# MCU.net
KiCad netlist of a schematic drawn in Altium Designer
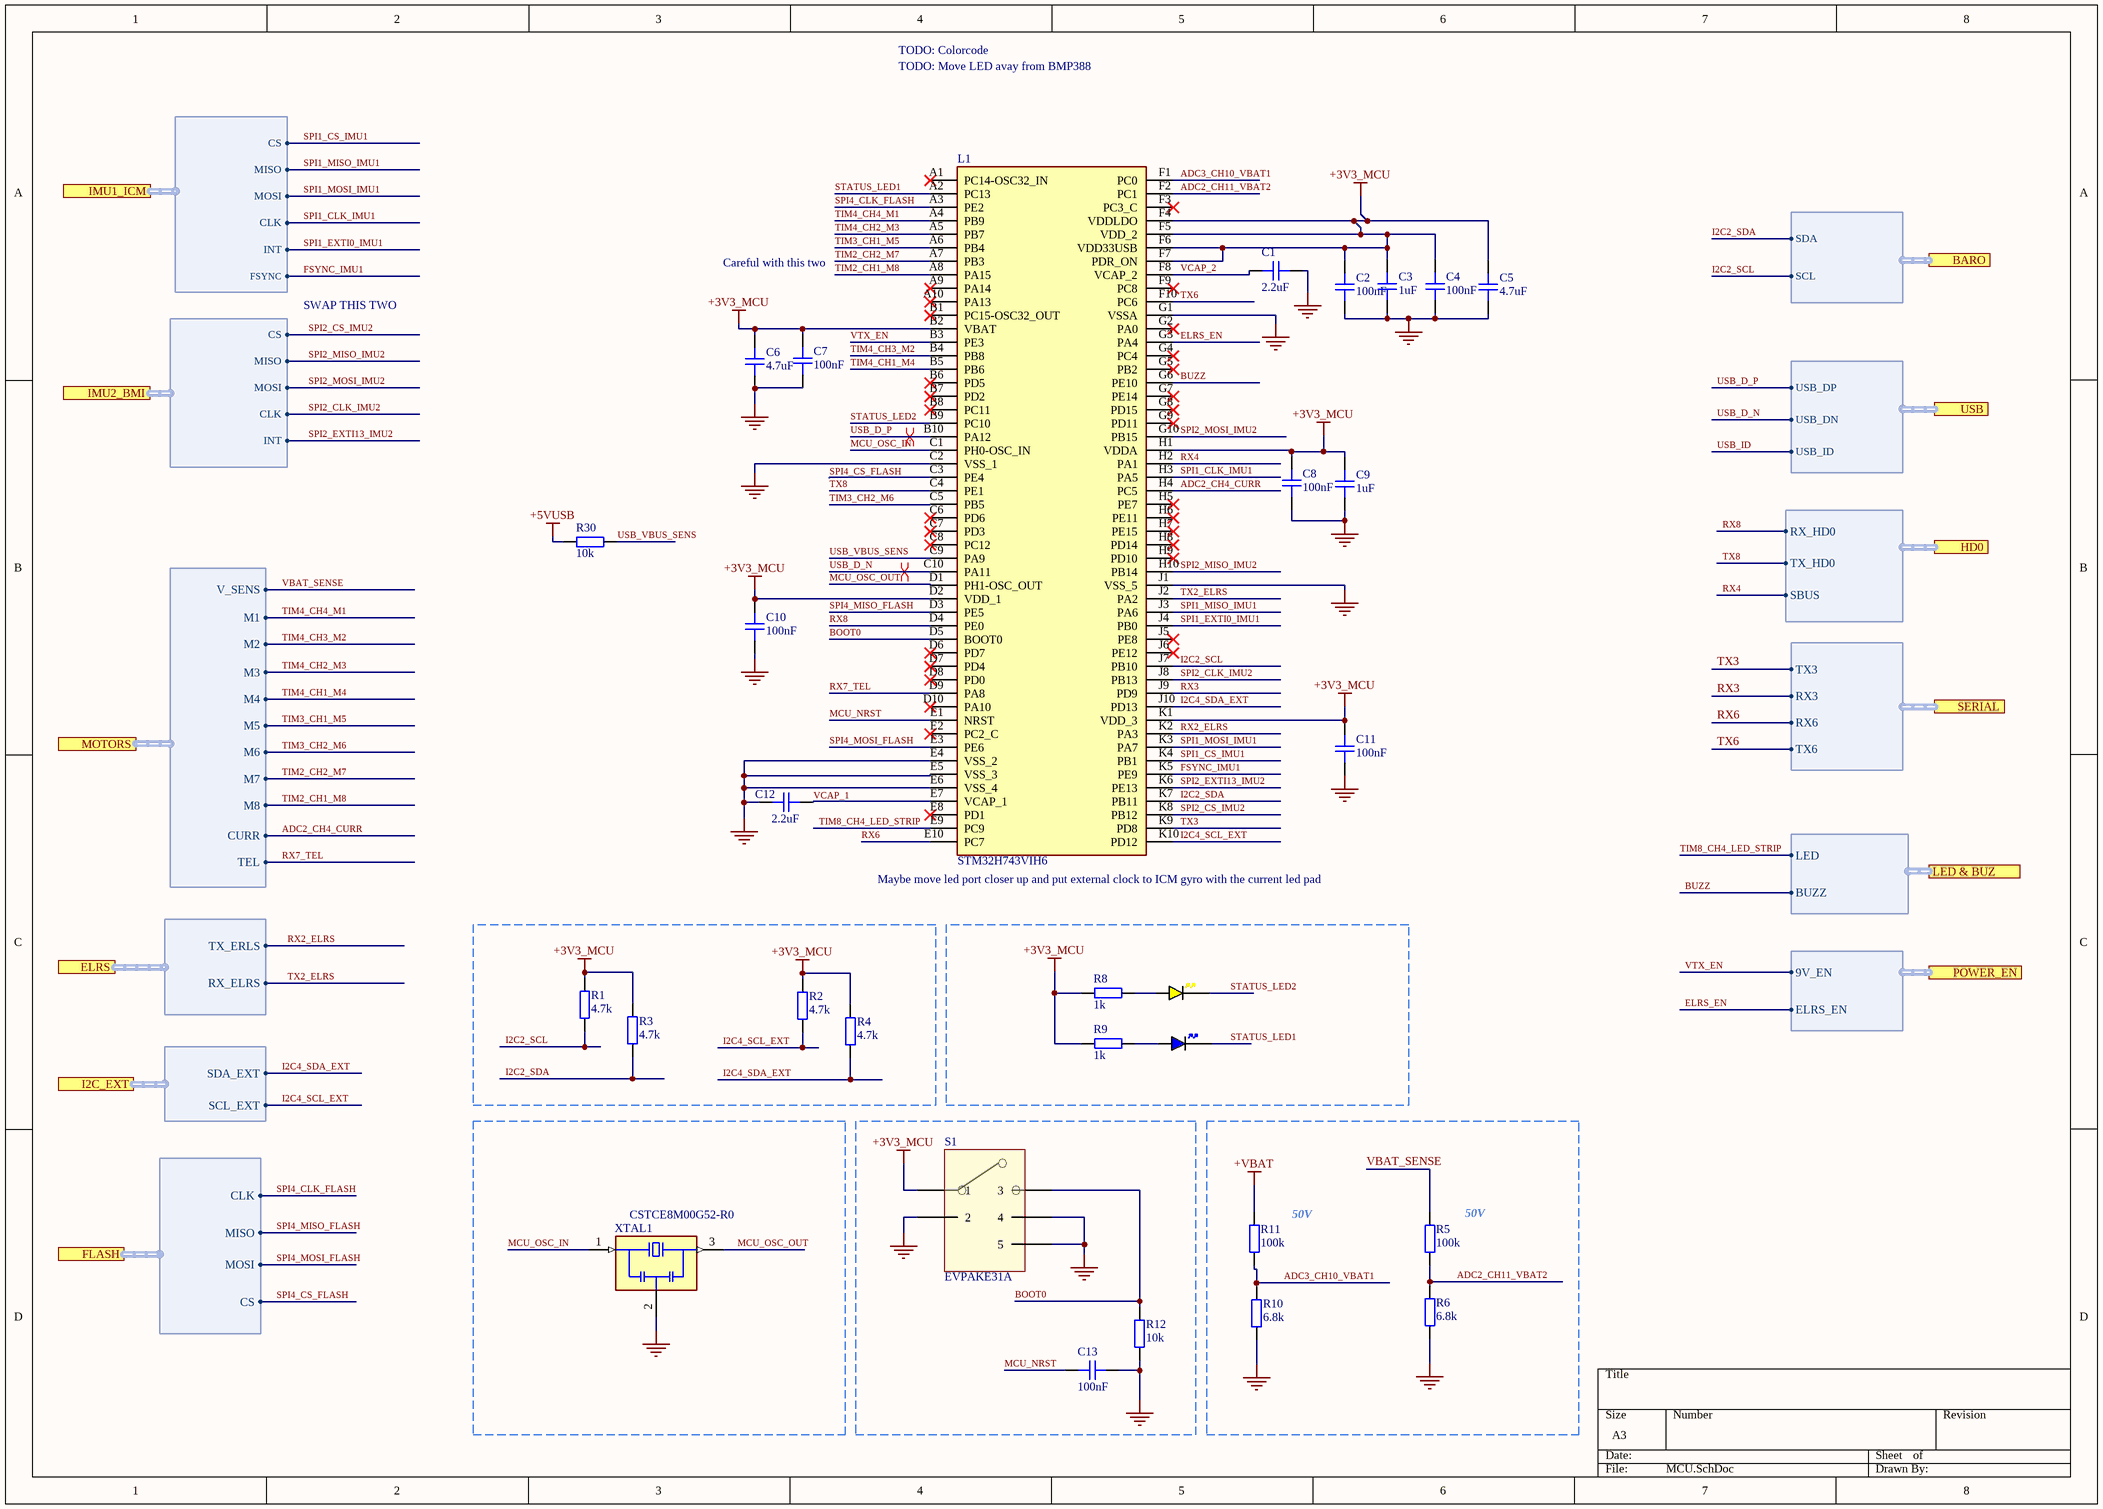
[diagram p0: MCU.SchDoc]

(export (version "E")
  (design (tool "Eeschema 10.0.6"))
  (components
    (comp (ref "C1")
      (value "2.2uF")
      (footprint "CAP_0402")
      (description "Capacitor SMD 0402")
      (libsource (lib "Schematic-Lib-PhilsLab") (part "CAP_0402"))
    )
    (comp (ref "C2")
      (value "100nF")
      (footprint "CAP_0201")
      (description "Capacitor SMD 0201")
      (libsource (lib "Schematic-Lib-PhilsLab") (part "CAP_0201"))
    )
    (comp (ref "C3")
      (value "1uF")
      (footprint "CAP_0402")
      (description "Capacitor SMD 0402")
      (libsource (lib "Schematic-Lib-PhilsLab") (part "CAP_0402"))
    )
    (comp (ref "C4")
      (value "100nF")
      (footprint "CAP_0201")
      (description "Capacitor SMD 0201")
      (libsource (lib "Schematic-Lib-PhilsLab") (part "CAP_0201"))
    )
    (comp (ref "C5")
      (value "4.7uF")
      (footprint "CAP_0402")
      (description "Capacitor SMD 0402")
      (libsource (lib "Schematic-Lib-PhilsLab") (part "CAP_0402"))
    )
    (comp (ref "C6")
      (value "4.7uF")
      (footprint "CAP_0402")
      (description "Capacitor SMD 0402")
      (libsource (lib "Schematic-Lib-PhilsLab") (part "CAP_0402"))
    )
    (comp (ref "C7")
      (value "100nF")
      (footprint "CAP_0201")
      (description "Capacitor SMD 0201")
      (libsource (lib "Schematic-Lib-PhilsLab") (part "CAP_0201"))
    )
    (comp (ref "C8")
      (value "100nF")
      (footprint "CAP_0201")
      (description "Capacitor SMD 0201")
      (libsource (lib "Schematic-Lib-PhilsLab") (part "CAP_0201"))
    )
    (comp (ref "C9")
      (value "1uF")
      (footprint "CAP_0402")
      (description "Capacitor SMD 0402")
      (libsource (lib "Schematic-Lib-PhilsLab") (part "CAP_0402"))
    )
    (comp (ref "C10")
      (value "100nF")
      (footprint "CAP_0201")
      (description "Capacitor SMD 0201")
      (libsource (lib "Schematic-Lib-PhilsLab") (part "CAP_0201"))
    )
    (comp (ref "C11")
      (value "100nF")
      (footprint "CAP_0201")
      (description "Capacitor SMD 0201")
      (libsource (lib "Schematic-Lib-PhilsLab") (part "CAP_0201"))
    )
    (comp (ref "C12")
      (value "2.2uF")
      (footprint "CAP_0402")
      (description "Capacitor SMD 0402")
      (libsource (lib "Schematic-Lib-PhilsLab") (part "CAP_0402"))
    )
    (comp (ref "C13")
      (value "100nF")
      (footprint "CAP_0201")
      (description "Capacitor SMD 0201")
      (libsource (lib "Schematic-Lib-PhilsLab") (part "CAP_0201"))
    )
    (comp (ref "L1")
      (value "STM32H743VIH6")
      (footprint "SamacSys:BGA100C80P10X10_800X800X110")
      (description "Inductor")
      (fields (field (name "MOUSER PART NUMBER") "511-STM32H743VIH6"))
      (libsource (lib "*") (part "STM32H743VIH6"))
    )
    (comp (ref "LED1")
      (value "YELLOW")
      (footprint "LED_0402_YELLOW")
      (description "LED 0402 YELLOW SMD")
      (libsource (lib "Schematic-Lib-PhilsLab") (part "LED_0402_YELLOW"))
    )
    (comp (ref "LED2")
      (value "BLUE")
      (footprint "LED_0402_BLUE")
      (description "LED 0402 BLUE SMD")
      (libsource (lib "Schematic-Lib-PhilsLab") (part "LED_0402_BLUE"))
    )
    (comp (ref "R1")
      (value "4.7k")
      (footprint "RES_0201")
      (description "Resistor SMD 0201")
      (libsource (lib "Schematic-Lib-PhilsLab") (part "RES_0201"))
    )
    (comp (ref "R2")
      (value "4.7k")
      (footprint "RES_0201")
      (description "Resistor SMD 0201")
      (libsource (lib "Schematic-Lib-PhilsLab") (part "RES_0201"))
    )
    (comp (ref "R3")
      (value "4.7k")
      (footprint "RES_0201")
      (description "Resistor SMD 0201")
      (libsource (lib "Schematic-Lib-PhilsLab") (part "RES_0201"))
    )
    (comp (ref "R4")
      (value "4.7k")
      (footprint "RES_0201")
      (description "Resistor SMD 0201")
      (libsource (lib "Schematic-Lib-PhilsLab") (part "RES_0201"))
    )
    (comp (ref "R5")
      (value "100k")
      (footprint "RES_0402")
      (description "Resistor SMD 0402")
      (libsource (lib "Schematic-Lib-PhilsLab") (part "RES_0402"))
    )
    (comp (ref "R6")
      (value "6.8k")
      (footprint "RES_0201")
      (description "Resistor SMD 0201")
      (libsource (lib "Schematic-Lib-PhilsLab") (part "RES_0201"))
    )
    (comp (ref "R8")
      (value "1k")
      (footprint "RES_0201")
      (description "Resistor SMD 0201")
      (libsource (lib "Schematic-Lib-PhilsLab") (part "RES_0201"))
    )
    (comp (ref "R9")
      (value "1k")
      (footprint "RES_0201")
      (description "Resistor SMD 0201")
      (libsource (lib "Schematic-Lib-PhilsLab") (part "RES_0201"))
    )
    (comp (ref "R10")
      (value "6.8k")
      (footprint "RES_0201")
      (description "Resistor SMD 0201")
      (libsource (lib "Schematic-Lib-PhilsLab") (part "RES_0201"))
    )
    (comp (ref "R11")
      (value "100k")
      (footprint "RES_0402")
      (description "Resistor SMD 0402")
      (libsource (lib "Schematic-Lib-PhilsLab") (part "RES_0402"))
    )
    (comp (ref "R12")
      (value "10k")
      (footprint "RES_0201")
      (description "Resistor SMD 0201")
      (libsource (lib "Schematic-Lib-PhilsLab") (part "RES_0201"))
    )
    (comp (ref "R30")
      (value "10k")
      (footprint "RES_0201")
      (description "Resistor SMD 0201")
      (libsource (lib "Schematic-Lib-PhilsLab") (part "RES_0201"))
    )
    (comp (ref "S1")
      (value "EVPAKE31A")
      (footprint "EVPAKE31A")
      (libsource (lib "Schematic-Lib-Singu") (part "EVPAKE31A"))
    )
    (comp (ref "XTAL1")
      (value "CSTCE8M00G52-R0")
      (footprint "OSC_CSTCE8M00G52-R0")
      (description "8MHz Ceramic Resonator Built in Capacitor 10pF Â±0.2% -20Â°C ~ 80Â°C Surface Mount")
      (fields (field (name "MF") "Murata"))
      (libsource (lib "Schematic-Lib-Singu") (part "CSTCE8M00G52-R0"))
    )
  )
  (nets
    (net (code "12") (name "+3V3_MCU") (class "Default")
      (node (ref "C10") (pin "2") (pinfunction "2_2") (pintype "passive"))
      (node (ref "C11") (pin "2") (pinfunction "2_2") (pintype "passive"))
      (node (ref "C2") (pin "2") (pinfunction "2_2") (pintype "passive"))
      (node (ref "C3") (pin "2") (pinfunction "2_2") (pintype "passive"))
      (node (ref "C4") (pin "2") (pinfunction "2_2") (pintype "passive"))
      (node (ref "C5") (pin "2") (pinfunction "2_2") (pintype "passive"))
      (node (ref "C6") (pin "2") (pinfunction "2_2") (pintype "passive"))
      (node (ref "C7") (pin "2") (pinfunction "2_2") (pintype "passive"))
      (node (ref "C8") (pin "2") (pinfunction "2_2") (pintype "passive"))
      (node (ref "C9") (pin "2") (pinfunction "2_2") (pintype "passive"))
      (node (ref "L1") (pin "B2") (pinfunction "VBAT_B2") (pintype "passive"))
      (node (ref "L1") (pin "D2") (pinfunction "VDD_1_D2") (pintype "passive"))
      (node (ref "L1") (pin "F4") (pinfunction "VDDLDO_F4") (pintype "passive"))
      (node (ref "L1") (pin "F5") (pinfunction "VDD_2_F5") (pintype "passive"))
      (node (ref "L1") (pin "F6") (pinfunction "VDD33USB_F6") (pintype "passive"))
      (node (ref "L1") (pin "F7") (pinfunction "PDR_ON_F7") (pintype "passive"))
      (node (ref "L1") (pin "H1") (pinfunction "VDDA_H1") (pintype "passive"))
      (node (ref "L1") (pin "K1") (pinfunction "VDD_3_K1") (pintype "passive"))
      (node (ref "R1") (pin "2") (pinfunction "2_2") (pintype "passive"))
      (node (ref "R2") (pin "2") (pinfunction "2_2") (pintype "passive"))
      (node (ref "R3") (pin "2") (pinfunction "2_2") (pintype "passive"))
      (node (ref "R4") (pin "2") (pinfunction "2_2") (pintype "passive"))
      (node (ref "R8") (pin "1") (pinfunction "1_1") (pintype "passive"))
      (node (ref "R9") (pin "1") (pinfunction "1_1") (pintype "passive"))
      (node (ref "S1") (pin "1") (pinfunction "1_1") (pintype "passive"))
    )
    (net (code "13") (name "+5VUSB") (class "Default")
      (node (ref "R30") (pin "1") (pinfunction "1_1") (pintype "passive"))
    )
    (net (code "14") (name "+VBAT") (class "Default")
      (node (ref "R11") (pin "2") (pinfunction "2_2") (pintype "passive"))
    )
    (net (code "16") (name "/ADC2_CH4_CURR") (class "Default")
      (node (ref "L1") (pin "H4") (pinfunction "PC5_H4") (pintype "passive"))
    )
    (net (code "17") (name "/ADC2_CH11_VBAT2") (class "Default")
      (node (ref "L1") (pin "F2") (pinfunction "PC1_F2") (pintype "passive"))
      (node (ref "R5") (pin "1") (pinfunction "1_1") (pintype "passive"))
      (node (ref "R6") (pin "2") (pinfunction "2_2") (pintype "passive"))
    )
    (net (code "18") (name "/ADC3_CH10_VBAT1") (class "Default")
      (node (ref "L1") (pin "F1") (pinfunction "PC0_F1") (pintype "passive"))
      (node (ref "R10") (pin "2") (pinfunction "2_2") (pintype "passive"))
      (node (ref "R11") (pin "1") (pinfunction "1_1") (pintype "passive"))
    )
    (net (code "19") (name "/BOOT0") (class "Default")
      (node (ref "L1") (pin "D5") (pinfunction "BOOT0_D5") (pintype "passive"))
      (node (ref "R12") (pin "2") (pinfunction "2_2") (pintype "passive"))
      (node (ref "S1") (pin "3") (pinfunction "3_3") (pintype "passive"))
    )
    (net (code "20") (name "/BUZZ") (class "Default")
      (node (ref "L1") (pin "G6") (pinfunction "PE10_G6") (pintype "passive"))
    )
    (net (code "21") (name "/ELRS_EN") (class "Default")
      (node (ref "L1") (pin "G3") (pinfunction "PA4_G3") (pintype "passive"))
    )
    (net (code "22") (name "/FSYNC_IMU1") (class "Default")
      (node (ref "L1") (pin "K5") (pinfunction "PE9_K5") (pintype "passive"))
    )
    (net (code "23") (name "/I2C2_SCL") (class "Default")
      (node (ref "L1") (pin "J7") (pinfunction "PB10_J7") (pintype "passive"))
      (node (ref "R1") (pin "1") (pinfunction "1_1") (pintype "passive"))
    )
    (net (code "24") (name "/I2C2_SDA") (class "Default")
      (node (ref "L1") (pin "K7") (pinfunction "PB11_K7") (pintype "passive"))
      (node (ref "R3") (pin "1") (pinfunction "1_1") (pintype "passive"))
    )
    (net (code "25") (name "/I2C4_SCL_EXT") (class "Default")
      (node (ref "L1") (pin "K10") (pinfunction "PD12_K10") (pintype "passive"))
      (node (ref "R2") (pin "1") (pinfunction "1_1") (pintype "passive"))
    )
    (net (code "26") (name "/I2C4_SDA_EXT") (class "Default")
      (node (ref "L1") (pin "J10") (pinfunction "PD13_J10") (pintype "passive"))
      (node (ref "R4") (pin "1") (pinfunction "1_1") (pintype "passive"))
    )
    (net (code "27") (name "/MCU_NRST") (class "Default")
      (node (ref "C13") (pin "1") (pinfunction "1_1") (pintype "passive"))
      (node (ref "L1") (pin "E1") (pinfunction "NRST_E1") (pintype "passive"))
    )
    (net (code "28") (name "/MCU_OSC_IN") (class "Default")
      (node (ref "L1") (pin "C1") (pinfunction "PH0-OSC_IN_C1") (pintype "passive"))
      (node (ref "XTAL1") (pin "1") (pinfunction "IN_1") (pintype "input"))
    )
    (net (code "29") (name "/MCU_OSC_OUT") (class "Default")
      (node (ref "L1") (pin "D1") (pinfunction "PH1-OSC_OUT_D1") (pintype "passive"))
      (node (ref "XTAL1") (pin "3") (pinfunction "OUT_3") (pintype "output"))
    )
    (net (code "30") (name "/RX2_ELRS") (class "Default")
      (node (ref "L1") (pin "K2") (pinfunction "PA3_K2") (pintype "passive"))
    )
    (net (code "31") (name "/RX3") (class "Default")
      (node (ref "L1") (pin "J9") (pinfunction "PD9_J9") (pintype "passive"))
    )
    (net (code "32") (name "/RX4") (class "Default")
      (node (ref "L1") (pin "H2") (pinfunction "PA1_H2") (pintype "passive"))
    )
    (net (code "33") (name "/RX6") (class "Default")
      (node (ref "L1") (pin "E10") (pinfunction "PC7_E10") (pintype "passive"))
    )
    (net (code "34") (name "/RX7_TEL") (class "Default")
      (node (ref "L1") (pin "D9") (pinfunction "PA8_D9") (pintype "passive"))
    )
    (net (code "35") (name "/RX8") (class "Default")
      (node (ref "L1") (pin "D4") (pinfunction "PE0_D4") (pintype "passive"))
    )
    (net (code "36") (name "/SPI1_CLK_IMU1") (class "Default")
      (node (ref "L1") (pin "H3") (pinfunction "PA5_H3") (pintype "passive"))
    )
    (net (code "37") (name "/SPI1_CS_IMU1") (class "Default")
      (node (ref "L1") (pin "K4") (pinfunction "PB1_K4") (pintype "passive"))
    )
    (net (code "38") (name "/SPI1_EXTI0_IMU1") (class "Default")
      (node (ref "L1") (pin "J4") (pinfunction "PB0_J4") (pintype "passive"))
    )
    (net (code "39") (name "/SPI1_MISO_IMU1") (class "Default")
      (node (ref "L1") (pin "J3") (pinfunction "PA6_J3") (pintype "passive"))
    )
    (net (code "40") (name "/SPI1_MOSI_IMU1") (class "Default")
      (node (ref "L1") (pin "K3") (pinfunction "PA7_K3") (pintype "passive"))
    )
    (net (code "41") (name "/SPI2_CLK_IMU2") (class "Default")
      (node (ref "L1") (pin "J8") (pinfunction "PB13_J8") (pintype "passive"))
    )
    (net (code "42") (name "/SPI2_CS_IMU2") (class "Default")
      (node (ref "L1") (pin "K8") (pinfunction "PB12_K8") (pintype "passive"))
    )
    (net (code "43") (name "/SPI2_EXTI13_IMU2") (class "Default")
      (node (ref "L1") (pin "K6") (pinfunction "PE13_K6") (pintype "passive"))
    )
    (net (code "44") (name "/SPI2_MISO_IMU2") (class "Default")
      (node (ref "L1") (pin "H10") (pinfunction "PB14_H10") (pintype "passive"))
    )
    (net (code "45") (name "/SPI2_MOSI_IMU2") (class "Default")
      (node (ref "L1") (pin "G10") (pinfunction "PB15_G10") (pintype "passive"))
    )
    (net (code "46") (name "/SPI4_CLK_FLASH") (class "Default")
      (node (ref "L1") (pin "A3") (pinfunction "PE2_A3") (pintype "passive"))
    )
    (net (code "47") (name "/SPI4_CS_FLASH") (class "Default")
      (node (ref "L1") (pin "C3") (pinfunction "PE4_C3") (pintype "passive"))
    )
    (net (code "48") (name "/SPI4_MISO_FLASH") (class "Default")
      (node (ref "L1") (pin "D3") (pinfunction "PE5_D3") (pintype "passive"))
    )
    (net (code "49") (name "/SPI4_MOSI_FLASH") (class "Default")
      (node (ref "L1") (pin "E3") (pinfunction "PE6_E3") (pintype "passive"))
    )
    (net (code "50") (name "/STATUS_LED1") (class "Default")
      (node (ref "L1") (pin "A2") (pinfunction "PC13_A2") (pintype "passive"))
      (node (ref "LED2") (pin "K") (pinfunction "K_K") (pintype "passive"))
    )
    (net (code "51") (name "/STATUS_LED2") (class "Default")
      (node (ref "L1") (pin "B9") (pinfunction "PC10_B9") (pintype "passive"))
      (node (ref "LED1") (pin "K") (pinfunction "K_K") (pintype "passive"))
    )
    (net (code "52") (name "/TIM2_CH1_M8") (class "Default")
      (node (ref "L1") (pin "A8") (pinfunction "PA15_A8") (pintype "passive"))
    )
    (net (code "53") (name "/TIM2_CH2_M7") (class "Default")
      (node (ref "L1") (pin "A7") (pinfunction "PB3_A7") (pintype "passive"))
    )
    (net (code "54") (name "/TIM3_CH1_M5") (class "Default")
      (node (ref "L1") (pin "A6") (pinfunction "PB4_A6") (pintype "passive"))
    )
    (net (code "55") (name "/TIM3_CH2_M6") (class "Default")
      (node (ref "L1") (pin "C5") (pinfunction "PB5_C5") (pintype "passive"))
    )
    (net (code "56") (name "/TIM4_CH1_M4") (class "Default")
      (node (ref "L1") (pin "B5") (pinfunction "PB6_B5") (pintype "passive"))
    )
    (net (code "57") (name "/TIM4_CH2_M3") (class "Default")
      (node (ref "L1") (pin "A5") (pinfunction "PB7_A5") (pintype "passive"))
    )
    (net (code "58") (name "/TIM4_CH3_M2") (class "Default")
      (node (ref "L1") (pin "B4") (pinfunction "PB8_B4") (pintype "passive"))
    )
    (net (code "59") (name "/TIM4_CH4_M1") (class "Default")
      (node (ref "L1") (pin "A4") (pinfunction "PB9_A4") (pintype "passive"))
    )
    (net (code "60") (name "/TIM8_CH4_LED_STRIP") (class "Default")
      (node (ref "L1") (pin "E9") (pinfunction "PC9_E9") (pintype "passive"))
    )
    (net (code "61") (name "/TX2_ELRS") (class "Default")
      (node (ref "L1") (pin "J2") (pinfunction "PA2_J2") (pintype "passive"))
    )
    (net (code "62") (name "/TX3") (class "Default")
      (node (ref "L1") (pin "K9") (pinfunction "PD8_K9") (pintype "passive"))
    )
    (net (code "63") (name "/TX6") (class "Default")
      (node (ref "L1") (pin "F10") (pinfunction "PC6_F10") (pintype "passive"))
    )
    (net (code "64") (name "/TX8") (class "Default")
      (node (ref "L1") (pin "C4") (pinfunction "PE1_C4") (pintype "passive"))
    )
    (net (code "65") (name "/USB_D_N") (class "Default")
      (node (ref "L1") (pin "C10") (pinfunction "PA11_C10") (pintype "passive"))
    )
    (net (code "66") (name "/USB_D_P") (class "Default")
      (node (ref "L1") (pin "B10") (pinfunction "PA12_B10") (pintype "passive"))
    )
    (net (code "68") (name "/USB_VBUS_SENS") (class "Default")
      (node (ref "L1") (pin "C9") (pinfunction "PA9_C9") (pintype "passive"))
      (node (ref "R30") (pin "2") (pinfunction "2_2") (pintype "passive"))
    )
    (net (code "69") (name "/VBAT_SENSE") (class "Default")
      (node (ref "R5") (pin "2") (pinfunction "2_2") (pintype "passive"))
    )
    (net (code "70") (name "/VCAP_1") (class "Default")
      (node (ref "C12") (pin "2") (pinfunction "2_2") (pintype "passive"))
      (node (ref "L1") (pin "E7") (pinfunction "VCAP_1_E7") (pintype "passive"))
    )
    (net (code "71") (name "/VCAP_2") (class "Default")
      (node (ref "C1") (pin "1") (pinfunction "1_1") (pintype "passive"))
      (node (ref "L1") (pin "F8") (pinfunction "VCAP_2_F8") (pintype "passive"))
    )
    (net (code "72") (name "/VTX_EN") (class "Default")
      (node (ref "L1") (pin "B3") (pinfunction "PE3_B3") (pintype "passive"))
    )
    (net (code "85") (name "GND") (class "Default")
      (node (ref "C1") (pin "2") (pinfunction "2_2") (pintype "passive"))
      (node (ref "C10") (pin "1") (pinfunction "1_1") (pintype "passive"))
      (node (ref "C11") (pin "1") (pinfunction "1_1") (pintype "passive"))
      (node (ref "C12") (pin "1") (pinfunction "1_1") (pintype "passive"))
      (node (ref "C13") (pin "2") (pinfunction "2_2") (pintype "passive"))
      (node (ref "C2") (pin "1") (pinfunction "1_1") (pintype "passive"))
      (node (ref "C3") (pin "1") (pinfunction "1_1") (pintype "passive"))
      (node (ref "C4") (pin "1") (pinfunction "1_1") (pintype "passive"))
      (node (ref "C5") (pin "1") (pinfunction "1_1") (pintype "passive"))
      (node (ref "C6") (pin "1") (pinfunction "1_1") (pintype "passive"))
      (node (ref "C7") (pin "1") (pinfunction "1_1") (pintype "passive"))
      (node (ref "C8") (pin "1") (pinfunction "1_1") (pintype "passive"))
      (node (ref "C9") (pin "1") (pinfunction "1_1") (pintype "passive"))
      (node (ref "L1") (pin "C2") (pinfunction "VSS_1_C2") (pintype "passive"))
      (node (ref "L1") (pin "E4") (pinfunction "VSS_2_E4") (pintype "passive"))
      (node (ref "L1") (pin "E5") (pinfunction "VSS_3_E5") (pintype "passive"))
      (node (ref "L1") (pin "E6") (pinfunction "VSS_4_E6") (pintype "passive"))
      (node (ref "L1") (pin "G1") (pinfunction "VSSA_G1") (pintype "passive"))
      (node (ref "L1") (pin "J1") (pinfunction "VSS_5_J1") (pintype "passive"))
      (node (ref "R10") (pin "1") (pinfunction "1_1") (pintype "passive"))
      (node (ref "R12") (pin "1") (pinfunction "1_1") (pintype "passive"))
      (node (ref "R6") (pin "1") (pinfunction "1_1") (pintype "passive"))
      (node (ref "S1") (pin "2") (pinfunction "2_2") (pintype "passive"))
      (node (ref "S1") (pin "4") (pinfunction "4_4") (pintype "passive"))
      (node (ref "S1") (pin "5") (pinfunction "5_5") (pintype "passive"))
      (node (ref "XTAL1") (pin "2") (pinfunction "GND_2") (pintype "power_in"))
    )
    (net (code "86") (name "Net-(LED1-PadA)") (class "Default")
      (node (ref "LED1") (pin "A") (pinfunction "A_A") (pintype "passive"))
      (node (ref "R8") (pin "2") (pinfunction "2_2") (pintype "passive"))
    )
    (net (code "87") (name "Net-(LED2-PadA)") (class "Default")
      (node (ref "LED2") (pin "A") (pinfunction "A_A") (pintype "passive"))
      (node (ref "R9") (pin "2") (pinfunction "2_2") (pintype "passive"))
    )
    (net (code "88") (name "unconnected-(L1-PA0-PadG2)") (class "Default")
      (node (ref "L1") (pin "G2") (pinfunction "PA0_G2") (pintype "passive+no_connect"))
    )
    (net (code "89") (name "unconnected-(L1-PA10-PadD10)") (class "Default")
      (node (ref "L1") (pin "D10") (pinfunction "PA10_D10") (pintype "passive+no_connect"))
    )
    (net (code "90") (name "unconnected-(L1-PA13-PadA10)") (class "Default")
      (node (ref "L1") (pin "A10") (pinfunction "PA13_A10") (pintype "passive+no_connect"))
    )
    (net (code "91") (name "unconnected-(L1-PA14-PadA9)") (class "Default")
      (node (ref "L1") (pin "A9") (pinfunction "PA14_A9") (pintype "passive+no_connect"))
    )
    (net (code "92") (name "unconnected-(L1-PB2-PadG5)") (class "Default")
      (node (ref "L1") (pin "G5") (pinfunction "PB2_G5") (pintype "passive+no_connect"))
    )
    (net (code "93") (name "unconnected-(L1-PC2_C-PadE2)") (class "Default")
      (node (ref "L1") (pin "E2") (pinfunction "PC2_C_E2") (pintype "passive+no_connect"))
    )
    (net (code "94") (name "unconnected-(L1-PC3_C-PadF3)") (class "Default")
      (node (ref "L1") (pin "F3") (pinfunction "PC3_C_F3") (pintype "passive+no_connect"))
    )
    (net (code "95") (name "unconnected-(L1-PC4-PadG4)") (class "Default")
      (node (ref "L1") (pin "G4") (pinfunction "PC4_G4") (pintype "passive+no_connect"))
    )
    (net (code "96") (name "unconnected-(L1-PC8-PadF9)") (class "Default")
      (node (ref "L1") (pin "F9") (pinfunction "PC8_F9") (pintype "passive+no_connect"))
    )
    (net (code "97") (name "unconnected-(L1-PC11-PadB8)") (class "Default")
      (node (ref "L1") (pin "B8") (pinfunction "PC11_B8") (pintype "passive+no_connect"))
    )
    (net (code "98") (name "unconnected-(L1-PC12-PadC8)") (class "Default")
      (node (ref "L1") (pin "C8") (pinfunction "PC12_C8") (pintype "passive+no_connect"))
    )
    (net (code "99") (name "unconnected-(L1-PC14-OSC32_IN-PadA1)") (class "Default")
      (node (ref "L1") (pin "A1") (pinfunction "PC14-OSC32_IN_A1") (pintype "passive+no_connect"))
    )
    (net (code "100") (name "unconnected-(L1-PC15-OSC32_OUT-PadB1)") (class "Default")
      (node (ref "L1") (pin "B1") (pinfunction "PC15-OSC32_OUT_B1") (pintype "passive+no_connect"))
    )
    (net (code "101") (name "unconnected-(L1-PD0-PadD8)") (class "Default")
      (node (ref "L1") (pin "D8") (pinfunction "PD0_D8") (pintype "passive+no_connect"))
    )
    (net (code "102") (name "unconnected-(L1-PD1-PadE8)") (class "Default")
      (node (ref "L1") (pin "E8") (pinfunction "PD1_E8") (pintype "passive+no_connect"))
    )
    (net (code "103") (name "unconnected-(L1-PD2-PadB7)") (class "Default")
      (node (ref "L1") (pin "B7") (pinfunction "PD2_B7") (pintype "passive+no_connect"))
    )
    (net (code "104") (name "unconnected-(L1-PD3-PadC7)") (class "Default")
      (node (ref "L1") (pin "C7") (pinfunction "PD3_C7") (pintype "passive+no_connect"))
    )
    (net (code "105") (name "unconnected-(L1-PD4-PadD7)") (class "Default")
      (node (ref "L1") (pin "D7") (pinfunction "PD4_D7") (pintype "passive+no_connect"))
    )
    (net (code "106") (name "unconnected-(L1-PD5-PadB6)") (class "Default")
      (node (ref "L1") (pin "B6") (pinfunction "PD5_B6") (pintype "passive+no_connect"))
    )
    (net (code "107") (name "unconnected-(L1-PD6-PadC6)") (class "Default")
      (node (ref "L1") (pin "C6") (pinfunction "PD6_C6") (pintype "passive+no_connect"))
    )
    (net (code "108") (name "unconnected-(L1-PD7-PadD6)") (class "Default")
      (node (ref "L1") (pin "D6") (pinfunction "PD7_D6") (pintype "passive+no_connect"))
    )
    (net (code "109") (name "unconnected-(L1-PD10-PadH9)") (class "Default")
      (node (ref "L1") (pin "H9") (pinfunction "PD10_H9") (pintype "passive+no_connect"))
    )
    (net (code "110") (name "unconnected-(L1-PD11-PadG9)") (class "Default")
      (node (ref "L1") (pin "G9") (pinfunction "PD11_G9") (pintype "passive+no_connect"))
    )
    (net (code "111") (name "unconnected-(L1-PD14-PadH8)") (class "Default")
      (node (ref "L1") (pin "H8") (pinfunction "PD14_H8") (pintype "passive+no_connect"))
    )
    (net (code "112") (name "unconnected-(L1-PD15-PadG8)") (class "Default")
      (node (ref "L1") (pin "G8") (pinfunction "PD15_G8") (pintype "passive+no_connect"))
    )
    (net (code "113") (name "unconnected-(L1-PE7-PadH5)") (class "Default")
      (node (ref "L1") (pin "H5") (pinfunction "PE7_H5") (pintype "passive+no_connect"))
    )
    (net (code "114") (name "unconnected-(L1-PE8-PadJ5)") (class "Default")
      (node (ref "L1") (pin "J5") (pinfunction "PE8_J5") (pintype "passive+no_connect"))
    )
    (net (code "115") (name "unconnected-(L1-PE11-PadH6)") (class "Default")
      (node (ref "L1") (pin "H6") (pinfunction "PE11_H6") (pintype "passive+no_connect"))
    )
    (net (code "116") (name "unconnected-(L1-PE12-PadJ6)") (class "Default")
      (node (ref "L1") (pin "J6") (pinfunction "PE12_J6") (pintype "passive+no_connect"))
    )
    (net (code "117") (name "unconnected-(L1-PE14-PadG7)") (class "Default")
      (node (ref "L1") (pin "G7") (pinfunction "PE14_G7") (pintype "passive+no_connect"))
    )
    (net (code "118") (name "unconnected-(L1-PE15-PadH7)") (class "Default")
      (node (ref "L1") (pin "H7") (pinfunction "PE15_H7") (pintype "passive+no_connect"))
    )
  )
)
